# midi.net
KiCad netlist of a schematic drawn in EAGLE
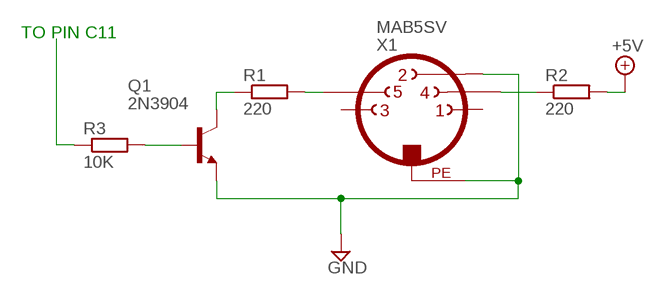
[diagram p0: schematic, sheet 1]

(export (version "E")
  (design (tool "Eeschema 10.0.6"))
  (components
    (comp (ref "Q1")
      (value "2N3904")
      (footprint "eagle-import:TO92")
      (libsource (lib "eagle-import") (part "2N3904"))
    )
    (comp (ref "R1")
      (value "220")
      (footprint "eagle-import:0309_12")
      (libsource (lib "eagle-import") (part "R-EU_0309/12"))
    )
    (comp (ref "R2")
      (value "220")
      (footprint "eagle-import:0309_12")
      (libsource (lib "eagle-import") (part "R-EU_0309/12"))
    )
    (comp (ref "R3")
      (value "10K")
      (footprint "eagle-import:0309_12")
      (libsource (lib "eagle-import") (part "R-EU_0309/12"))
    )
    (comp (ref "X1")
      (value "MAB5SV")
      (footprint "eagle-import:MAB5SV")
      (libsource (lib "eagle-import") (part "MAB5SV"))
    )
  )
  (nets
    (net (code "1") (name "+5V") (class "Default")
      (node (ref "R2") (pin "2") (pinfunction "2_2") (pintype "passive"))
    )
    (net (code "2") (name "GND") (class "Default")
      (node (ref "Q1") (pin "3") (pinfunction "E_3") (pintype "passive"))
      (node (ref "X1") (pin "2") (pinfunction "2_2") (pintype "passive"))
      (node (ref "X1") (pin "PE") (pinfunction "PE_PE") (pintype "power_in"))
    )
    (net (code "3") (name "Net-(Q1-B)") (class "Default")
      (node (ref "Q1") (pin "2") (pinfunction "B_2") (pintype "passive"))
      (node (ref "R3") (pin "2") (pinfunction "2_2") (pintype "passive"))
    )
    (net (code "4") (name "Net-(Q1-C)") (class "Default")
      (node (ref "Q1") (pin "1") (pinfunction "C_1") (pintype "passive"))
      (node (ref "R1") (pin "1") (pinfunction "1_1") (pintype "passive"))
    )
    (net (code "5") (name "Net-(R1-Pad2)") (class "Default")
      (node (ref "R1") (pin "2") (pinfunction "2_2") (pintype "passive"))
      (node (ref "X1") (pin "5") (pinfunction "5_5") (pintype "passive"))
    )
    (net (code "6") (name "Net-(R2-Pad1)") (class "Default")
      (node (ref "R2") (pin "1") (pinfunction "1_1") (pintype "passive"))
      (node (ref "X1") (pin "4") (pinfunction "4_4") (pintype "passive"))
    )
    (net (code "7") (name "unconnected-(R3-Pad1)") (class "Default")
      (node (ref "R3") (pin "1") (pinfunction "1_1") (pintype "passive"))
    )
    (net (code "8") (name "unconnected-(X1-Pad1)") (class "Default")
      (node (ref "X1") (pin "1") (pinfunction "1_1") (pintype "passive"))
    )
    (net (code "9") (name "unconnected-(X1-Pad3)") (class "Default")
      (node (ref "X1") (pin "3") (pinfunction "3_3") (pintype "passive"))
    )
  )
)
